# WB-v2_0b.net
KiCad netlist of a schematic drawn in EAGLE
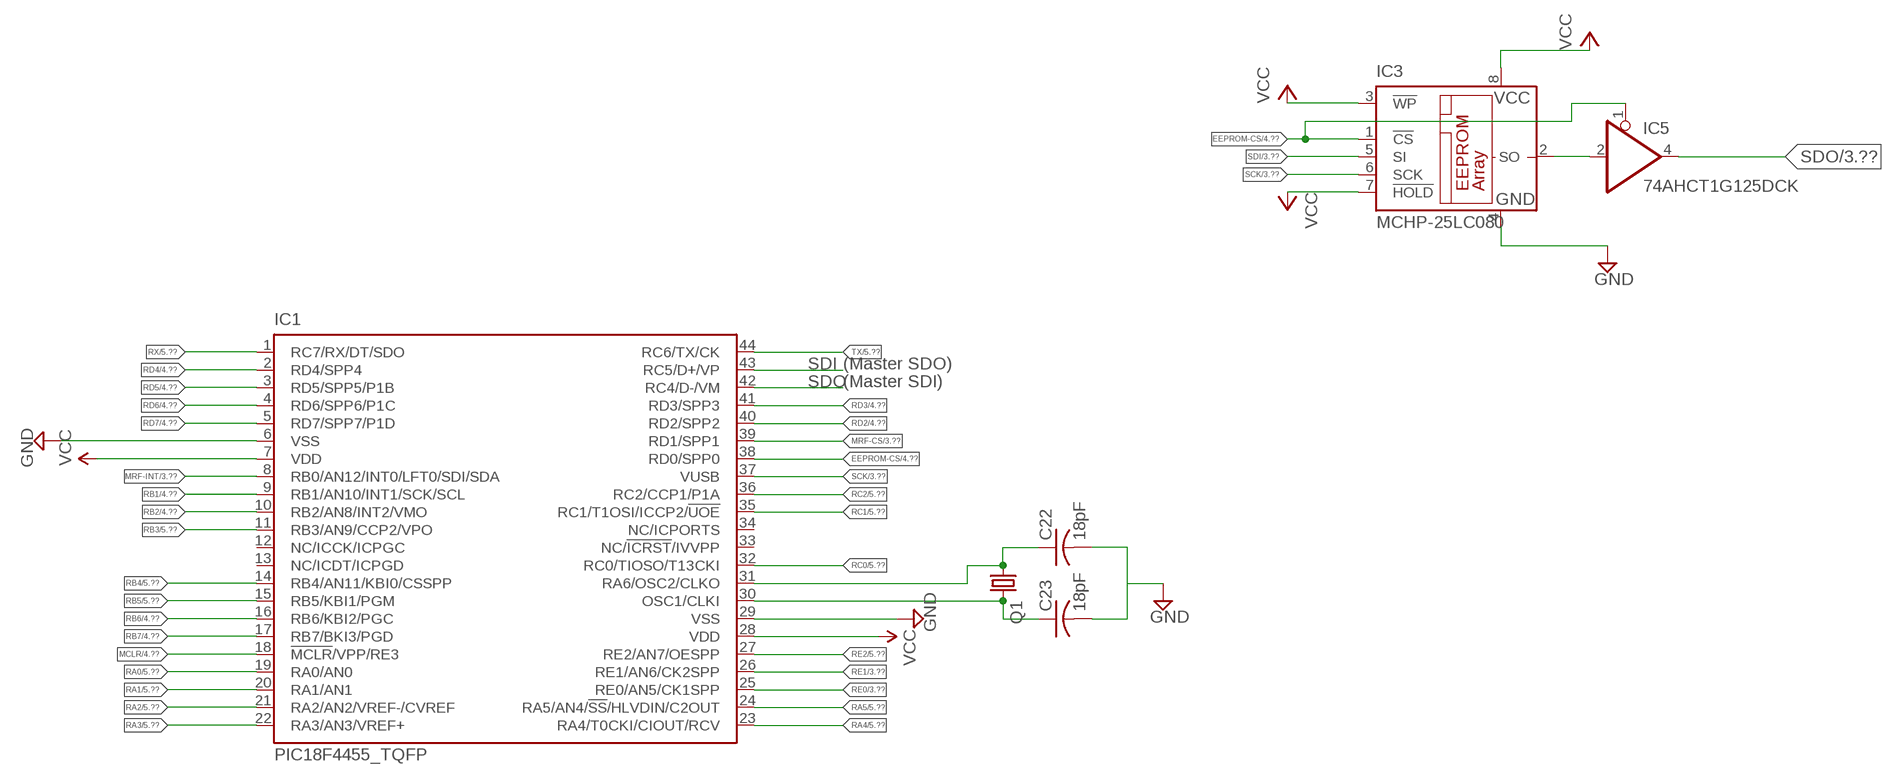
[diagram p0: schematic, sheet 1]
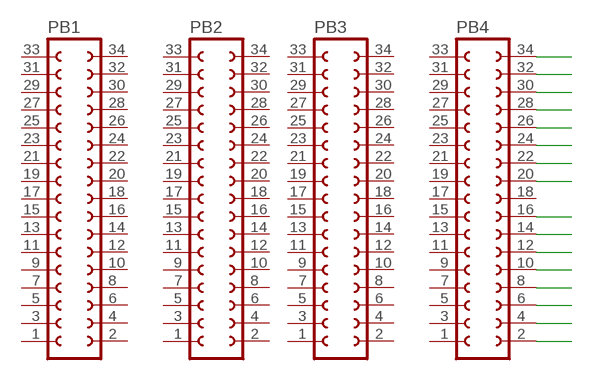
[diagram p1: schematic, sheet 2]
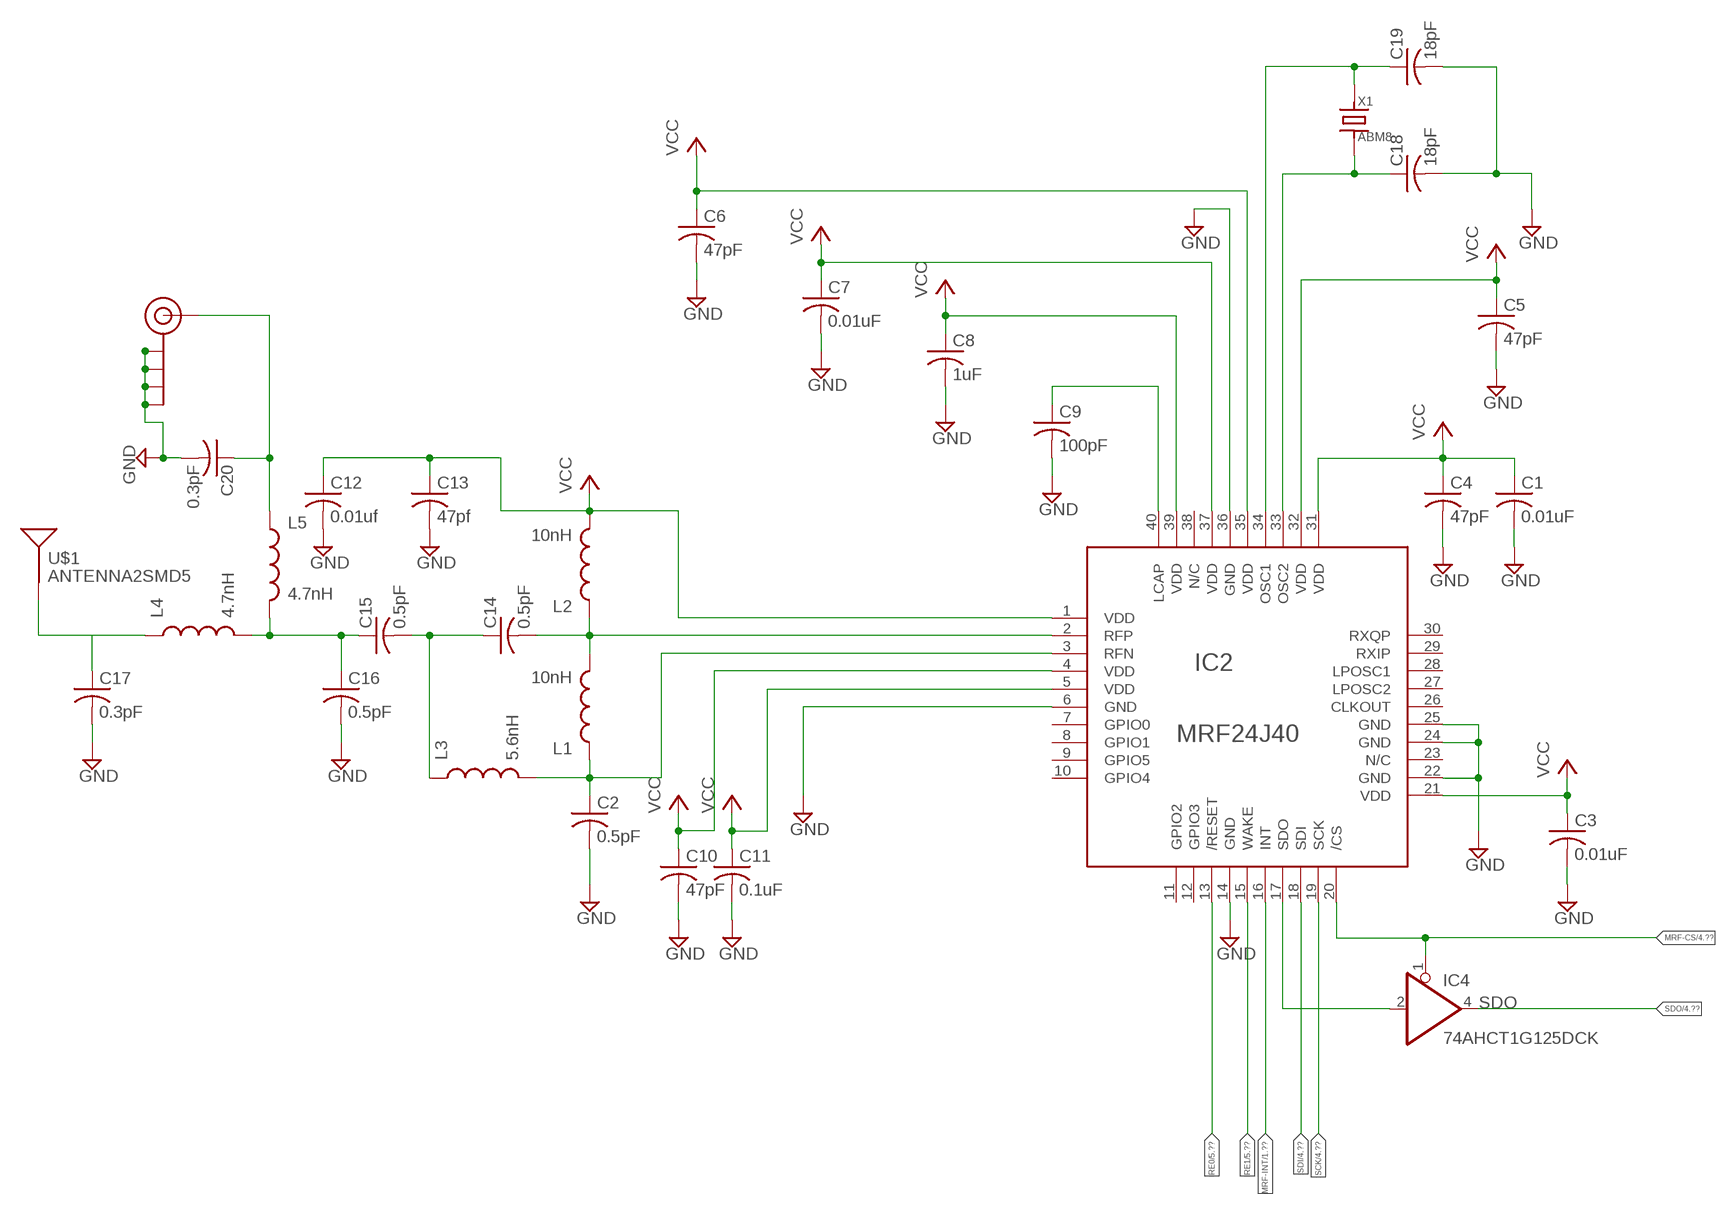
[diagram p2: schematic, sheet 3]
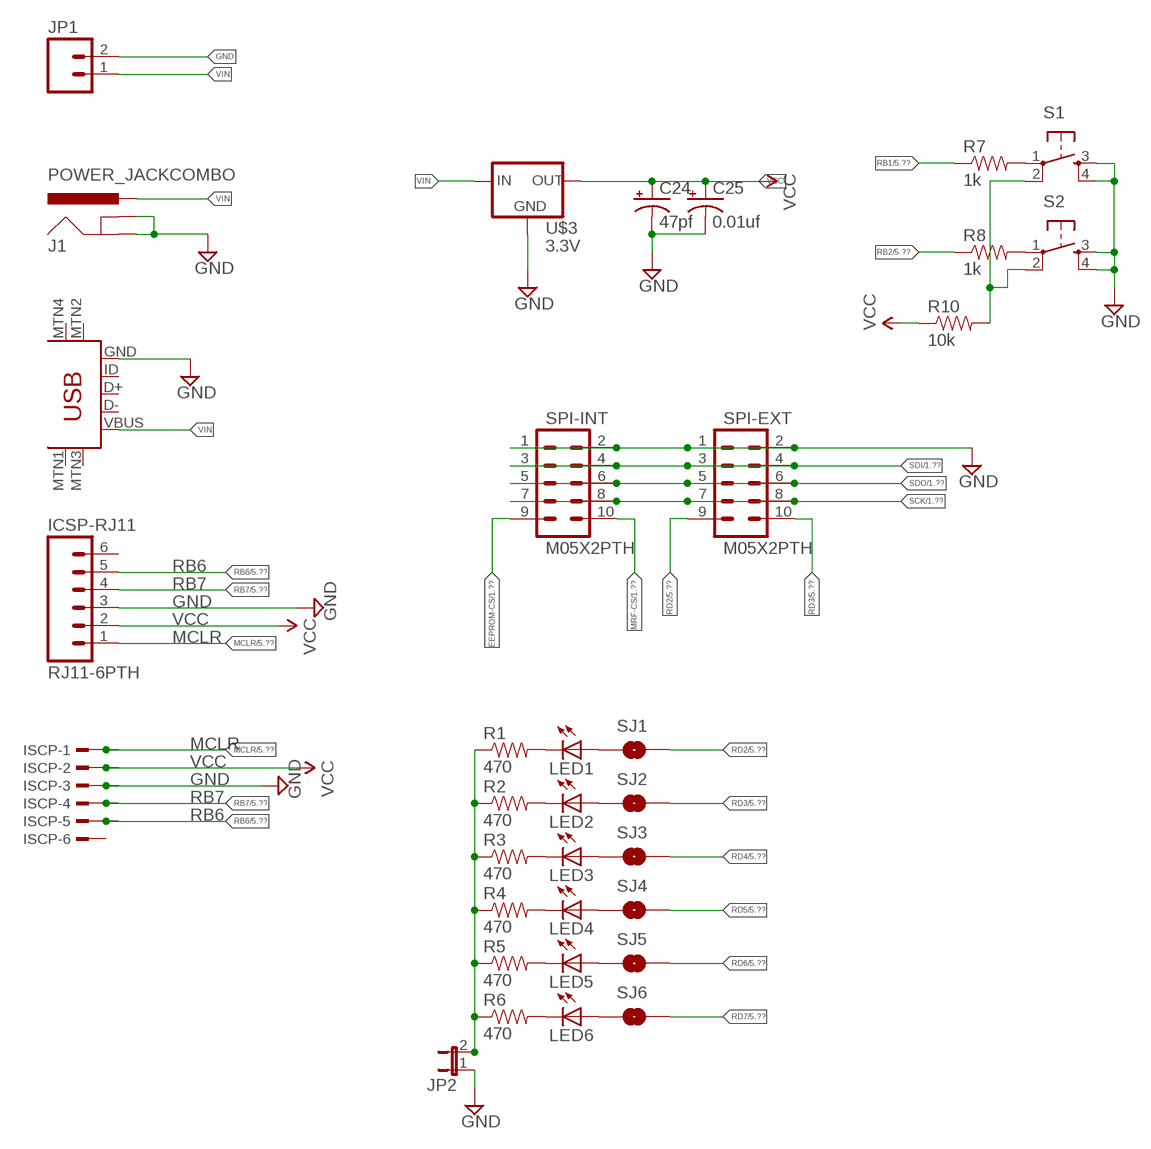
[diagram p3: schematic, sheet 4]
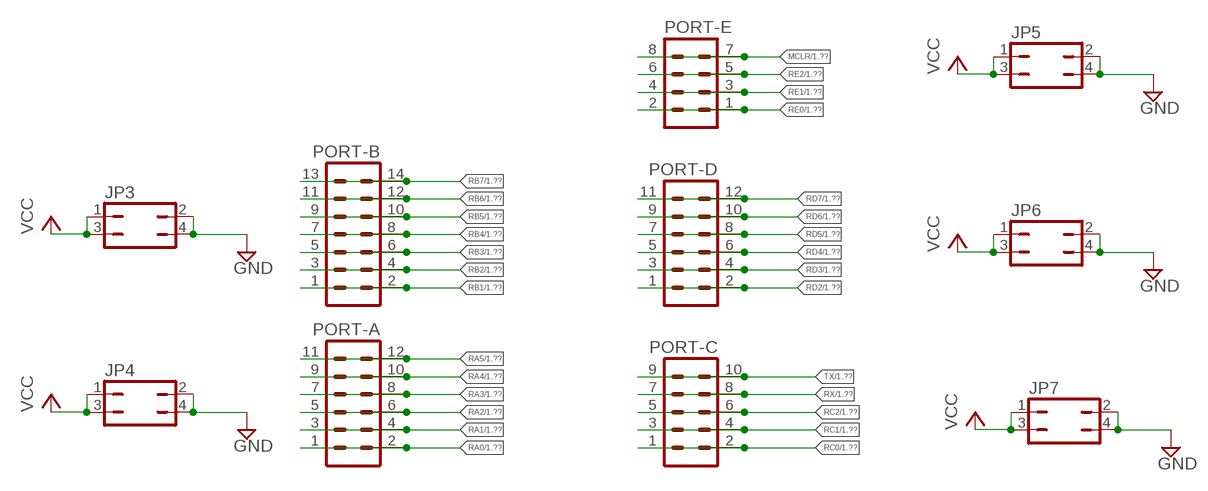
[diagram p4: schematic, sheet 5]

(export (version "E")
  (design (tool "Eeschema 10.0.6"))
  (components
    (comp (ref "C1")
      (value "0.01uF")
      (footprint "eagle-import:C0402")
      (libsource (lib "eagle-import") (part "C-USC0402"))
    )
    (comp (ref "C2")
      (value "0.5pF")
      (footprint "eagle-import:C0402")
      (libsource (lib "eagle-import") (part "C-USC0402"))
    )
    (comp (ref "C3")
      (value "0.01uF")
      (footprint "eagle-import:C0402")
      (libsource (lib "eagle-import") (part "C-USC0402"))
    )
    (comp (ref "C4")
      (value "47pF")
      (footprint "eagle-import:C0402")
      (libsource (lib "eagle-import") (part "C-USC0402"))
    )
    (comp (ref "C5")
      (value "47pF")
      (footprint "eagle-import:C0402")
      (libsource (lib "eagle-import") (part "C-USC0402"))
    )
    (comp (ref "C6")
      (value "47pF")
      (footprint "eagle-import:C0402")
      (libsource (lib "eagle-import") (part "C-USC0402"))
    )
    (comp (ref "C7")
      (value "0.01uF")
      (footprint "eagle-import:C0402")
      (libsource (lib "eagle-import") (part "C-USC0402"))
    )
    (comp (ref "C8")
      (value "1uF")
      (footprint "eagle-import:C0402")
      (libsource (lib "eagle-import") (part "C-USC0402"))
    )
    (comp (ref "C9")
      (value "100pF")
      (footprint "eagle-import:C0402")
      (libsource (lib "eagle-import") (part "C-USC0402"))
    )
    (comp (ref "C10")
      (value "47pF")
      (footprint "eagle-import:C0402")
      (libsource (lib "eagle-import") (part "C-USC0402"))
    )
    (comp (ref "C11")
      (value "0.1uF")
      (footprint "eagle-import:C0402")
      (libsource (lib "eagle-import") (part "C-USC0402"))
    )
    (comp (ref "C12")
      (value "0.01uf")
      (footprint "eagle-import:C0402")
      (libsource (lib "eagle-import") (part "C-USC0402"))
    )
    (comp (ref "C13")
      (value "47pf")
      (footprint "eagle-import:C0402")
      (libsource (lib "eagle-import") (part "C-USC0402"))
    )
    (comp (ref "C14")
      (value "0.5pF")
      (footprint "eagle-import:C0402")
      (libsource (lib "eagle-import") (part "C-USC0402"))
    )
    (comp (ref "C15")
      (value "0.5pF")
      (footprint "eagle-import:C0402")
      (libsource (lib "eagle-import") (part "C-USC0402"))
    )
    (comp (ref "C16")
      (value "0.5pF")
      (footprint "eagle-import:C0402")
      (libsource (lib "eagle-import") (part "C-USC0402"))
    )
    (comp (ref "C17")
      (value "0.3pF")
      (footprint "eagle-import:C0402")
      (libsource (lib "eagle-import") (part "C-USC0402"))
    )
    (comp (ref "C18")
      (value "18pF")
      (footprint "eagle-import:C0402")
      (libsource (lib "eagle-import") (part "C-USC0402"))
    )
    (comp (ref "C19")
      (value "18pF")
      (footprint "eagle-import:C0402")
      (libsource (lib "eagle-import") (part "C-USC0402"))
    )
    (comp (ref "C20")
      (value "0.3pF")
      (footprint "eagle-import:C0402")
      (libsource (lib "eagle-import") (part "C-USC0402"))
    )
    (comp (ref "IC2")
      (value "MRF24J40")
      (footprint "eagle-import:QFN40")
      (libsource (lib "eagle-import") (part "MRF24J40"))
    )
    (comp (ref "IC4")
      (value "74AHCT1G125DCK")
      (footprint "eagle-import:SC70-5")
      (libsource (lib "eagle-import") (part "741G125DCKAHCT"))
    )
    (comp (ref "J$1")
      (value "SMA_EDGE")
      (footprint "eagle-import:SMA-EDGE")
      (libsource (lib "eagle-import") (part "SMA_EDGE"))
    )
    (comp (ref "L1")
      (value "10nH")
      (footprint "eagle-import:C0402")
      (libsource (lib "eagle-import") (part "INDUCTOR0402"))
    )
    (comp (ref "L2")
      (value "10nH")
      (footprint "eagle-import:C0402")
      (libsource (lib "eagle-import") (part "INDUCTOR0402"))
    )
    (comp (ref "L3")
      (value "5.6nH")
      (footprint "eagle-import:C0402")
      (libsource (lib "eagle-import") (part "INDUCTOR0402"))
    )
    (comp (ref "L4")
      (value "4.7nH")
      (footprint "eagle-import:C0402")
      (libsource (lib "eagle-import") (part "INDUCTOR0402"))
    )
    (comp (ref "L5")
      (value "4.7nH")
      (footprint "eagle-import:C0402")
      (libsource (lib "eagle-import") (part "INDUCTOR0402"))
    )
    (comp (ref "U$1")
      (value "ANTENNA2SMD5")
      (footprint "eagle-import:ANTENNA-CHIP5")
      (libsource (lib "eagle-import") (part "ANTENNA2SMD5"))
    )
    (comp (ref "X1")
      (value "ABM8")
      (footprint "eagle-import:ABM8")
      (libsource (lib "eagle-import") (part "ABM8"))
    )
    (comp (ref "PB1")
      (value "FE17-2")
      (footprint "eagle-import:FE17-2")
      (libsource (lib "eagle-import") (part "FE17-2"))
    )
    (comp (ref "PB2")
      (value "FE17-2")
      (footprint "eagle-import:FE17-2")
      (libsource (lib "eagle-import") (part "FE17-2"))
    )
    (comp (ref "PB3")
      (value "FE17-2")
      (footprint "eagle-import:FE17-2")
      (libsource (lib "eagle-import") (part "FE17-2"))
    )
    (comp (ref "PB4")
      (value "FE17-2")
      (footprint "eagle-import:FE17-2")
      (libsource (lib "eagle-import") (part "FE17-2"))
    )
    (comp (ref "JP3")
      (value "JP2Q")
      (footprint "eagle-import:JP2Q")
      (libsource (lib "eagle-import") (part "JP2Q"))
    )
    (comp (ref "JP4")
      (value "JP2Q")
      (footprint "eagle-import:JP2Q")
      (libsource (lib "eagle-import") (part "JP2Q"))
    )
    (comp (ref "JP5")
      (value "JP2Q")
      (footprint "eagle-import:JP2Q")
      (libsource (lib "eagle-import") (part "JP2Q"))
    )
    (comp (ref "JP6")
      (value "JP2Q")
      (footprint "eagle-import:JP2Q")
      (libsource (lib "eagle-import") (part "JP2Q"))
    )
    (comp (ref "JP7")
      (value "JP2Q")
      (footprint "eagle-import:JP2Q")
      (libsource (lib "eagle-import") (part "JP2Q"))
    )
    (comp (ref "PORT-A")
      (value "MA06-2")
      (footprint "eagle-import:MA06-2")
      (libsource (lib "eagle-import") (part "MA06-2"))
    )
    (comp (ref "PORT-B")
      (value "MA07-2")
      (footprint "eagle-import:MA07-2")
      (libsource (lib "eagle-import") (part "MA07-2"))
    )
    (comp (ref "PORT-C")
      (value "MA05-2")
      (footprint "eagle-import:MA05-2")
      (libsource (lib "eagle-import") (part "MA05-2"))
    )
    (comp (ref "PORT-D")
      (value "MA06-2")
      (footprint "eagle-import:MA06-2")
      (libsource (lib "eagle-import") (part "MA06-2"))
    )
    (comp (ref "PORT-E")
      (value "MA04-2")
      (footprint "eagle-import:MA04-2")
      (libsource (lib "eagle-import") (part "MA04-2"))
    )
    (comp (ref "C22")
      (value "18pF")
      (footprint "eagle-import:C0402")
      (libsource (lib "eagle-import") (part "C-USC0402"))
    )
    (comp (ref "C23")
      (value "18pF")
      (footprint "eagle-import:C0402")
      (libsource (lib "eagle-import") (part "C-USC0402"))
    )
    (comp (ref "IC1")
      (value "PIC18F4455_TQFP")
      (footprint "eagle-import:TQFP44")
      (fields (field (name "MF") "MICROCHIP") (field (name "MPN") "PIC18F4455-I/PT"))
      (libsource (lib "eagle-import") (part "PIC18F4_TQFP455"))
    )
    (comp (ref "IC3")
      (value "MCHP-25LC080")
      (footprint "eagle-import:SO-08")
      (fields (field (name "MF") "MICROCHIP") (field (name "MPN") "25AA080/SN"))
      (libsource (lib "eagle-import") (part "25SNAA080"))
    )
    (comp (ref "IC5")
      (value "74AHCT1G125DCK")
      (footprint "eagle-import:SC70-5")
      (libsource (lib "eagle-import") (part "741G125DCKAHCT"))
    )
    (comp (ref "Q1")
      (value "CRYSTALSM49")
      (footprint "eagle-import:SM49")
      (libsource (lib "eagle-import") (part "CRYSTALSM49"))
    )
    (comp (ref "C24")
      (value "47pf")
      (footprint "eagle-import:CPOL-RADIAL-10UF-25V")
      (libsource (lib "eagle-import") (part "CAP_POLPTH2"))
    )
    (comp (ref "C25")
      (value "0.01uf")
      (footprint "eagle-import:CPOL-RADIAL-10UF-25V")
      (libsource (lib "eagle-import") (part "CAP_POLPTH2"))
    )
    (comp (ref "ICSP-RJ11")
      (value "RJ11-6PTH")
      (footprint "eagle-import:RJ11-6")
      (libsource (lib "eagle-import") (part "RJ11-6PTH"))
    )
    (comp (ref "ISCP")
      (value "TSW-106-02-S-S")
      (footprint "eagle-import:TSW-106-02-S-S")
      (libsource (lib "eagle-import") (part "TSW-106-02-S-S"))
    )
    (comp (ref "J1")
      (value "POWER_JACKCOMBO")
      (footprint "eagle-import:POWER_JACK_COMBO")
      (libsource (lib "eagle-import") (part "POWER_JACKCOMBO"))
    )
    (comp (ref "JP1")
      (value "M02LOCK_LONGPADS")
      (footprint "eagle-import:1X02_LOCK_LONGPADS")
      (libsource (lib "eagle-import") (part "M02LOCK_LONGPADS"))
    )
    (comp (ref "JP2")
      (value "JUMPER-2PTH")
      (footprint "eagle-import:1X02")
      (libsource (lib "eagle-import") (part "JUMPER-2PTH"))
    )
    (comp (ref "LED1")
      (value "LED0603")
      (footprint "eagle-import:LED-0603")
      (libsource (lib "eagle-import") (part "LED0603"))
    )
    (comp (ref "LED2")
      (value "LED0603")
      (footprint "eagle-import:LED-0603")
      (libsource (lib "eagle-import") (part "LED0603"))
    )
    (comp (ref "LED3")
      (value "LED0603")
      (footprint "eagle-import:LED-0603")
      (libsource (lib "eagle-import") (part "LED0603"))
    )
    (comp (ref "LED4")
      (value "LED0603")
      (footprint "eagle-import:LED-0603")
      (libsource (lib "eagle-import") (part "LED0603"))
    )
    (comp (ref "LED5")
      (value "LED0603")
      (footprint "eagle-import:LED-0603")
      (libsource (lib "eagle-import") (part "LED0603"))
    )
    (comp (ref "LED6")
      (value "LED0603")
      (footprint "eagle-import:LED-0603")
      (libsource (lib "eagle-import") (part "LED0603"))
    )
    (comp (ref "R1")
      (value "470")
      (footprint "eagle-import:0603-RES")
      (libsource (lib "eagle-import") (part "RESISTOR0603-RES"))
    )
    (comp (ref "R2")
      (value "470")
      (footprint "eagle-import:0603-RES")
      (libsource (lib "eagle-import") (part "RESISTOR0603-RES"))
    )
    (comp (ref "R3")
      (value "470")
      (footprint "eagle-import:0603-RES")
      (libsource (lib "eagle-import") (part "RESISTOR0603-RES"))
    )
    (comp (ref "R4")
      (value "470")
      (footprint "eagle-import:0603-RES")
      (libsource (lib "eagle-import") (part "RESISTOR0603-RES"))
    )
    (comp (ref "R5")
      (value "470")
      (footprint "eagle-import:0603-RES")
      (libsource (lib "eagle-import") (part "RESISTOR0603-RES"))
    )
    (comp (ref "R6")
      (value "470")
      (footprint "eagle-import:0603-RES")
      (libsource (lib "eagle-import") (part "RESISTOR0603-RES"))
    )
    (comp (ref "R7")
      (value "1k")
      (footprint "eagle-import:0603-RES")
      (libsource (lib "eagle-import") (part "RESISTOR0603-RES"))
    )
    (comp (ref "R8")
      (value "1k")
      (footprint "eagle-import:0603-RES")
      (libsource (lib "eagle-import") (part "RESISTOR0603-RES"))
    )
    (comp (ref "R10")
      (value "10k")
      (footprint "eagle-import:0603-RES")
      (libsource (lib "eagle-import") (part "RESISTOR0603-RES"))
    )
    (comp (ref "S1")
      (value "TAC_SWITCHPTH")
      (footprint "eagle-import:TACTILE-PTH")
      (libsource (lib "eagle-import") (part "TAC_SWITCHPTH"))
    )
    (comp (ref "S2")
      (value "TAC_SWITCHPTH")
      (footprint "eagle-import:TACTILE-PTH")
      (libsource (lib "eagle-import") (part "TAC_SWITCHPTH"))
    )
    (comp (ref "SJ1")
      (value "SOLDERJUMPERTRACE")
      (footprint "eagle-import:SJ_2S-TRACE")
      (libsource (lib "eagle-import") (part "SOLDERJUMPERTRACE"))
    )
    (comp (ref "SJ2")
      (value "SOLDERJUMPERTRACE")
      (footprint "eagle-import:SJ_2S-TRACE")
      (libsource (lib "eagle-import") (part "SOLDERJUMPERTRACE"))
    )
    (comp (ref "SJ3")
      (value "SOLDERJUMPERTRACE")
      (footprint "eagle-import:SJ_2S-TRACE")
      (libsource (lib "eagle-import") (part "SOLDERJUMPERTRACE"))
    )
    (comp (ref "SJ4")
      (value "SOLDERJUMPERTRACE")
      (footprint "eagle-import:SJ_2S-TRACE")
      (libsource (lib "eagle-import") (part "SOLDERJUMPERTRACE"))
    )
    (comp (ref "SJ5")
      (value "SOLDERJUMPERTRACE")
      (footprint "eagle-import:SJ_2S-TRACE")
      (libsource (lib "eagle-import") (part "SOLDERJUMPERTRACE"))
    )
    (comp (ref "SJ6")
      (value "SOLDERJUMPERTRACE")
      (footprint "eagle-import:SJ_2S-TRACE")
      (libsource (lib "eagle-import") (part "SOLDERJUMPERTRACE"))
    )
    (comp (ref "SPI-EXT")
      (value "M05X2PTH")
      (footprint "eagle-import:AVR_ICSP")
      (libsource (lib "eagle-import") (part "M05X2PTH"))
    )
    (comp (ref "SPI-INT")
      (value "M05X2PTH")
      (footprint "eagle-import:AVR_ICSP")
      (libsource (lib "eagle-import") (part "M05X2PTH"))
    )
    (comp (ref "U$2")
      (value "USB-MINIB-5PIN")
      (footprint "eagle-import:USB-MINIB")
      (libsource (lib "eagle-import") (part "USB-MINIB-5PIN"))
    )
    (comp (ref "U$3")
      (value "3.3V")
      (footprint "eagle-import:78XXL")
      (libsource (lib "eagle-import") (part "V_REG_LD1117VXX"))
    )
  )
  (nets
    (net (code "1") (name "EEPROM-CS") (class "Default")
      (node (ref "IC1") (pin "38") (pinfunction "RD0/SPP0_38") (pintype "bidirectional"))
      (node (ref "IC3") (pin "1") (pinfunction "~{CS}_1") (pintype "input"))
      (node (ref "IC5") (pin "1") (pinfunction "OE_1") (pintype "input"))
      (node (ref "SPI-INT") (pin "9") (pinfunction "9_9") (pintype "passive"))
    )
    (net (code "2") (name "GND") (class "Default")
      (node (ref "C1") (pin "2") (pinfunction "2_2") (pintype "passive"))
      (node (ref "C10") (pin "2") (pinfunction "2_2") (pintype "passive"))
      (node (ref "C11") (pin "2") (pinfunction "2_2") (pintype "passive"))
      (node (ref "C12") (pin "2") (pinfunction "2_2") (pintype "passive"))
      (node (ref "C13") (pin "2") (pinfunction "2_2") (pintype "passive"))
      (node (ref "C16") (pin "2") (pinfunction "2_2") (pintype "passive"))
      (node (ref "C17") (pin "2") (pinfunction "2_2") (pintype "passive"))
      (node (ref "C18") (pin "2") (pinfunction "2_2") (pintype "passive"))
      (node (ref "C19") (pin "2") (pinfunction "2_2") (pintype "passive"))
      (node (ref "C2") (pin "2") (pinfunction "2_2") (pintype "passive"))
      (node (ref "C20") (pin "2") (pinfunction "2_2") (pintype "passive"))
      (node (ref "C22") (pin "2") (pinfunction "2_2") (pintype "passive"))
      (node (ref "C23") (pin "2") (pinfunction "2_2") (pintype "passive"))
      (node (ref "C24") (pin "2") (pinfunction "-_2") (pintype "passive"))
      (node (ref "C25") (pin "2") (pinfunction "-_2") (pintype "passive"))
      (node (ref "C3") (pin "2") (pinfunction "2_2") (pintype "passive"))
      (node (ref "C4") (pin "2") (pinfunction "2_2") (pintype "passive"))
      (node (ref "C5") (pin "2") (pinfunction "2_2") (pintype "passive"))
      (node (ref "C6") (pin "2") (pinfunction "2_2") (pintype "passive"))
      (node (ref "C7") (pin "2") (pinfunction "2_2") (pintype "passive"))
      (node (ref "C8") (pin "2") (pinfunction "2_2") (pintype "passive"))
      (node (ref "C9") (pin "2") (pinfunction "2_2") (pintype "passive"))
      (node (ref "IC1") (pin "29") (pinfunction "VSS_29") (pintype "power_in"))
      (node (ref "IC1") (pin "6") (pinfunction "VSS_6") (pintype "power_in"))
      (node (ref "IC2") (pin "14") (pinfunction "GND_14") (pintype "power_in"))
      (node (ref "IC2") (pin "22") (pinfunction "GND_22") (pintype "power_in"))
      (node (ref "IC2") (pin "24") (pinfunction "GND_24") (pintype "power_in"))
      (node (ref "IC2") (pin "25") (pinfunction "GND_25") (pintype "power_in"))
      (node (ref "IC2") (pin "36") (pinfunction "GND_36") (pintype "power_in"))
      (node (ref "IC2") (pin "6") (pinfunction "GND_6") (pintype "power_in"))
      (node (ref "IC3") (pin "4") (pinfunction "GND_4") (pintype "power_in"))
      (node (ref "ICSP-RJ11") (pin "3") (pinfunction "3_3") (pintype "passive"))
      (node (ref "ISCP") (pin "3") (pinfunction "1_3") (pintype "passive"))
      (node (ref "J$1") (pin "GND@0") (pinfunction "GND_GND@0") (pintype "bidirectional"))
      (node (ref "J$1") (pin "GND@1") (pinfunction "GND_GND@1") (pintype "bidirectional"))
      (node (ref "J$1") (pin "GND@2") (pinfunction "GND_GND@2") (pintype "bidirectional"))
      (node (ref "J$1") (pin "GND@3") (pinfunction "GND_GND@3") (pintype "bidirectional"))
      (node (ref "J1") (pin "GND") (pinfunction "GNDBREAK_GND") (pintype "bidirectional"))
      (node (ref "J1") (pin "GND@1") (pinfunction "GND_GND@1") (pintype "bidirectional"))
      (node (ref "JP1") (pin "2") (pinfunction "2_2") (pintype "passive"))
      (node (ref "JP2") (pin "1") (pinfunction "1_1") (pintype "passive"))
      (node (ref "JP3") (pin "2") (pinfunction "2_2") (pintype "passive"))
      (node (ref "JP3") (pin "4") (pinfunction "4_4") (pintype "passive"))
      (node (ref "JP4") (pin "2") (pinfunction "2_2") (pintype "passive"))
      (node (ref "JP4") (pin "4") (pinfunction "4_4") (pintype "passive"))
      (node (ref "JP5") (pin "2") (pinfunction "2_2") (pintype "passive"))
      (node (ref "JP5") (pin "4") (pinfunction "4_4") (pintype "passive"))
      (node (ref "JP6") (pin "2") (pinfunction "2_2") (pintype "passive"))
      (node (ref "JP6") (pin "4") (pinfunction "4_4") (pintype "passive"))
      (node (ref "JP7") (pin "2") (pinfunction "2_2") (pintype "passive"))
      (node (ref "JP7") (pin "4") (pinfunction "4_4") (pintype "passive"))
      (node (ref "S1") (pin "3") (pinfunction "3_3") (pintype "passive"))
      (node (ref "S1") (pin "4") (pinfunction "4_4") (pintype "passive"))
      (node (ref "S2") (pin "3") (pinfunction "3_3") (pintype "passive"))
      (node (ref "S2") (pin "4") (pinfunction "4_4") (pintype "passive"))
      (node (ref "SPI-EXT") (pin "1") (pinfunction "1_1") (pintype "passive"))
      (node (ref "SPI-EXT") (pin "2") (pinfunction "2_2") (pintype "passive"))
      (node (ref "SPI-INT") (pin "1") (pinfunction "1_1") (pintype "passive"))
      (node (ref "SPI-INT") (pin "2") (pinfunction "2_2") (pintype "passive"))
      (node (ref "U$2") (pin "GND") (pinfunction "GND_GND") (pintype "bidirectional"))
      (node (ref "U$3") (pin "IN") (pinfunction "GND_IN") (pintype "input"))
    )
    (net (code "3") (name "MCLR") (class "Default")
      (node (ref "IC1") (pin "18") (pinfunction "~{MCLR}/VPP/RE3_18") (pintype "input"))
      (node (ref "ICSP-RJ11") (pin "1") (pinfunction "1_1") (pintype "passive"))
      (node (ref "ISCP") (pin "1") (pinfunction "1_1") (pintype "passive"))
      (node (ref "PORT-E") (pin "7") (pinfunction "7_7") (pintype "passive"))
      (node (ref "PORT-E") (pin "8") (pinfunction "8_8") (pintype "passive"))
    )
    (net (code "4") (name "MRF-CS") (class "Default")
      (node (ref "IC1") (pin "39") (pinfunction "RD1/SPP1_39") (pintype "bidirectional"))
      (node (ref "IC2") (pin "20") (pinfunction "/CS_20") (pintype "bidirectional"))
      (node (ref "IC4") (pin "1") (pinfunction "OE_1") (pintype "input"))
      (node (ref "SPI-INT") (pin "10") (pinfunction "10_10") (pintype "passive"))
    )
    (net (code "5") (name "MRF-INT") (class "Default")
      (node (ref "IC1") (pin "8") (pinfunction "RB0/AN12/INT0/LFT0/SDI/SDA_8") (pintype "bidirectional"))
      (node (ref "IC2") (pin "16") (pinfunction "INT_16") (pintype "bidirectional"))
    )
    (net (code "6") (name "Net-(C14-Pad1)") (class "Default")
      (node (ref "C14") (pin "1") (pinfunction "1_1") (pintype "passive"))
      (node (ref "C15") (pin "2") (pinfunction "2_2") (pintype "passive"))
      (node (ref "L3") (pin "1") (pinfunction "1_1") (pintype "passive"))
    )
    (net (code "7") (name "Net-(C15-Pad1)") (class "Default")
      (node (ref "C15") (pin "1") (pinfunction "1_1") (pintype "passive"))
      (node (ref "C16") (pin "1") (pinfunction "1_1") (pintype "passive"))
      (node (ref "L4") (pin "2") (pinfunction "2_2") (pintype "passive"))
      (node (ref "L5") (pin "2") (pinfunction "2_2") (pintype "passive"))
    )
    (net (code "8") (name "Net-(IC1-OSC1{slash}CLKI)") (class "Default")
      (node (ref "C23") (pin "1") (pinfunction "1_1") (pintype "passive"))
      (node (ref "IC1") (pin "30") (pinfunction "OSC1/CLKI_30") (pintype "input"))
      (node (ref "Q1") (pin "2") (pinfunction "2_2") (pintype "passive"))
    )
    (net (code "9") (name "Net-(IC1-RA6{slash}OSC2{slash}CLKO)") (class "Default")
      (node (ref "C22") (pin "1") (pinfunction "1_1") (pintype "passive"))
      (node (ref "IC1") (pin "31") (pinfunction "RA6/OSC2/CLKO_31") (pintype "output"))
      (node (ref "Q1") (pin "1") (pinfunction "1_1") (pintype "passive"))
    )
    (net (code "10") (name "Net-(IC2-LCAP)") (class "Default")
      (node (ref "C9") (pin "1") (pinfunction "1_1") (pintype "passive"))
      (node (ref "IC2") (pin "40") (pinfunction "LCAP_40") (pintype "bidirectional"))
    )
    (net (code "11") (name "Net-(IC2-OSC1)") (class "Default")
      (node (ref "C19") (pin "1") (pinfunction "1_1") (pintype "passive"))
      (node (ref "IC2") (pin "34") (pinfunction "OSC1_34") (pintype "open_collector"))
      (node (ref "X1") (pin "P$3") (pinfunction "P$3_P$3") (pintype "bidirectional"))
    )
    (net (code "12") (name "Net-(IC2-OSC2)") (class "Default")
      (node (ref "C18") (pin "1") (pinfunction "1_1") (pintype "passive"))
      (node (ref "IC2") (pin "33") (pinfunction "OSC2_33") (pintype "open_collector"))
      (node (ref "X1") (pin "P$1") (pinfunction "P$1_P$1") (pintype "bidirectional"))
    )
    (net (code "13") (name "Net-(IC2-RFN)") (class "Default")
      (node (ref "C2") (pin "1") (pinfunction "1_1") (pintype "passive"))
      (node (ref "IC2") (pin "3") (pinfunction "RFN_3") (pintype "bidirectional"))
      (node (ref "L1") (pin "1") (pinfunction "1_1") (pintype "passive"))
      (node (ref "L3") (pin "2") (pinfunction "2_2") (pintype "passive"))
    )
    (net (code "14") (name "Net-(IC2-RFP)") (class "Default")
      (node (ref "C14") (pin "2") (pinfunction "2_2") (pintype "passive"))
      (node (ref "IC2") (pin "2") (pinfunction "RFP_2") (pintype "bidirectional"))
      (node (ref "L1") (pin "2") (pinfunction "2_2") (pintype "passive"))
      (node (ref "L2") (pin "1") (pinfunction "1_1") (pintype "passive"))
    )
    (net (code "15") (name "Net-(IC2-SDO)") (class "Default")
      (node (ref "IC2") (pin "17") (pinfunction "SDO_17") (pintype "bidirectional"))
      (node (ref "IC4") (pin "2") (pinfunction "I_2") (pintype "input"))
    )
    (net (code "16") (name "Net-(IC3-SO)") (class "Default")
      (node (ref "IC3") (pin "2") (pinfunction "SO_2") (pintype "bidirectional"))
      (node (ref "IC5") (pin "2") (pinfunction "I_2") (pintype "input"))
    )
    (net (code "17") (name "Net-(J$1-SIGNAL)") (class "Default")
      (node (ref "C20") (pin "1") (pinfunction "1_1") (pintype "passive"))
      (node (ref "J$1") (pin "SIG") (pinfunction "SIGNAL_SIG") (pintype "bidirectional"))
      (node (ref "L5") (pin "1") (pinfunction "1_1") (pintype "passive"))
    )
    (net (code "18") (name "Net-(JP2-Pad2)") (class "Default")
      (node (ref "JP2") (pin "2") (pinfunction "2_2") (pintype "passive"))
      (node (ref "R1") (pin "1") (pinfunction "1_1") (pintype "passive"))
      (node (ref "R2") (pin "1") (pinfunction "1_1") (pintype "passive"))
      (node (ref "R3") (pin "1") (pinfunction "1_1") (pintype "passive"))
      (node (ref "R4") (pin "1") (pinfunction "1_1") (pintype "passive"))
      (node (ref "R5") (pin "1") (pinfunction "1_1") (pintype "passive"))
      (node (ref "R6") (pin "1") (pinfunction "1_1") (pintype "passive"))
    )
    (net (code "19") (name "Net-(LED1-PadA)") (class "Default")
      (node (ref "LED1") (pin "A") (pinfunction "A_A") (pintype "passive"))
      (node (ref "SJ1") (pin "1") (pinfunction "1_1") (pintype "passive"))
    )
    (net (code "20") (name "Net-(LED1-PadC)") (class "Default")
      (node (ref "LED1") (pin "C") (pinfunction "C_C") (pintype "passive"))
      (node (ref "R1") (pin "2") (pinfunction "2_2") (pintype "passive"))
    )
    (net (code "21") (name "Net-(LED2-PadA)") (class "Default")
      (node (ref "LED2") (pin "A") (pinfunction "A_A") (pintype "passive"))
      (node (ref "SJ2") (pin "1") (pinfunction "1_1") (pintype "passive"))
    )
    (net (code "22") (name "Net-(LED2-PadC)") (class "Default")
      (node (ref "LED2") (pin "C") (pinfunction "C_C") (pintype "passive"))
      (node (ref "R2") (pin "2") (pinfunction "2_2") (pintype "passive"))
    )
    (net (code "23") (name "Net-(LED3-PadA)") (class "Default")
      (node (ref "LED3") (pin "A") (pinfunction "A_A") (pintype "passive"))
      (node (ref "SJ3") (pin "1") (pinfunction "1_1") (pintype "passive"))
    )
    (net (code "24") (name "Net-(LED3-PadC)") (class "Default")
      (node (ref "LED3") (pin "C") (pinfunction "C_C") (pintype "passive"))
      (node (ref "R3") (pin "2") (pinfunction "2_2") (pintype "passive"))
    )
    (net (code "25") (name "Net-(LED4-PadA)") (class "Default")
      (node (ref "LED4") (pin "A") (pinfunction "A_A") (pintype "passive"))
      (node (ref "SJ4") (pin "1") (pinfunction "1_1") (pintype "passive"))
    )
    (net (code "26") (name "Net-(LED4-PadC)") (class "Default")
      (node (ref "LED4") (pin "C") (pinfunction "C_C") (pintype "passive"))
      (node (ref "R4") (pin "2") (pinfunction "2_2") (pintype "passive"))
    )
    (net (code "27") (name "Net-(LED5-PadA)") (class "Default")
      (node (ref "LED5") (pin "A") (pinfunction "A_A") (pintype "passive"))
      (node (ref "SJ5") (pin "1") (pinfunction "1_1") (pintype "passive"))
    )
    (net (code "28") (name "Net-(LED5-PadC)") (class "Default")
      (node (ref "LED5") (pin "C") (pinfunction "C_C") (pintype "passive"))
      (node (ref "R5") (pin "2") (pinfunction "2_2") (pintype "passive"))
    )
    (net (code "29") (name "Net-(LED6-PadA)") (class "Default")
      (node (ref "LED6") (pin "A") (pinfunction "A_A") (pintype "passive"))
      (node (ref "SJ6") (pin "1") (pinfunction "1_1") (pintype "passive"))
    )
    (net (code "30") (name "Net-(LED6-PadC)") (class "Default")
      (node (ref "LED6") (pin "C") (pinfunction "C_C") (pintype "passive"))
      (node (ref "R6") (pin "2") (pinfunction "2_2") (pintype "passive"))
    )
    (net (code "31") (name "Net-(R7-Pad2)") (class "Default")
      (node (ref "R7") (pin "2") (pinfunction "2_2") (pintype "passive"))
      (node (ref "S1") (pin "1") (pinfunction "1_1") (pintype "passive"))
    )
    (net (code "32") (name "Net-(R8-Pad2)") (class "Default")
      (node (ref "R8") (pin "2") (pinfunction "2_2") (pintype "passive"))
      (node (ref "S2") (pin "1") (pinfunction "1_1") (pintype "passive"))
    )
    (net (code "33") (name "Net-(R10-Pad2)") (class "Default")
      (node (ref "R10") (pin "2") (pinfunction "2_2") (pintype "passive"))
      (node (ref "S1") (pin "2") (pinfunction "2_2") (pintype "passive"))
      (node (ref "S2") (pin "2") (pinfunction "2_2") (pintype "passive"))
    )
    (net (code "34") (name "Net-(U$1-SIGNAL)") (class "Default")
      (node (ref "C17") (pin "1") (pinfunction "1_1") (pintype "passive"))
      (node (ref "L4") (pin "1") (pinfunction "1_1") (pintype "passive"))
      (node (ref "U$1") (pin "FEED") (pinfunction "SIGNAL_FEED") (pintype "bidirectional"))
    )
    (net (code "35") (name "RA0") (class "Default")
      (node (ref "IC1") (pin "19") (pinfunction "RA0/AN0_19") (pintype "bidirectional"))
      (node (ref "PORT-A") (pin "1") (pinfunction "1_1") (pintype "passive"))
      (node (ref "PORT-A") (pin "2") (pinfunction "2_2") (pintype "passive"))
    )
    (net (code "36") (name "RA1") (class "Default")
      (node (ref "IC1") (pin "20") (pinfunction "RA1/AN1_20") (pintype "bidirectional"))
      (node (ref "PORT-A") (pin "3") (pinfunction "3_3") (pintype "passive"))
      (node (ref "PORT-A") (pin "4") (pinfunction "4_4") (pintype "passive"))
    )
    (net (code "37") (name "RA2") (class "Default")
      (node (ref "IC1") (pin "21") (pinfunction "RA2/AN2/VREF-/CVREF_21") (pintype "bidirectional"))
      (node (ref "PORT-A") (pin "5") (pinfunction "5_5") (pintype "passive"))
      (node (ref "PORT-A") (pin "6") (pinfunction "6_6") (pintype "passive"))
    )
    (net (code "38") (name "RA3") (class "Default")
      (node (ref "IC1") (pin "22") (pinfunction "RA3/AN3/VREF+_22") (pintype "bidirectional"))
      (node (ref "PORT-A") (pin "7") (pinfunction "7_7") (pintype "passive"))
      (node (ref "PORT-A") (pin "8") (pinfunction "8_8") (pintype "passive"))
    )
    (net (code "39") (name "RA4") (class "Default")
      (node (ref "IC1") (pin "23") (pinfunction "RA4/T0CKI/CIOUT/RCV_23") (pintype "bidirectional"))
      (node (ref "PORT-A") (pin "10") (pinfunction "10_10") (pintype "passive"))
      (node (ref "PORT-A") (pin "9") (pinfunction "9_9") (pintype "passive"))
    )
    (net (code "40") (name "RA5") (class "Default")
      (node (ref "IC1") (pin "24") (pinfunction "RA5/AN4/~{SS}/HLVDIN/C2OUT_24") (pintype "bidirectional"))
      (node (ref "PORT-A") (pin "11") (pinfunction "11_11") (pintype "passive"))
      (node (ref "PORT-A") (pin "12") (pinfunction "12_12") (pintype "passive"))
    )
    (net (code "41") (name "RB1") (class "Default")
      (node (ref "IC1") (pin "9") (pinfunction "RB1/AN10/INT1/SCK/SCL_9") (pintype "bidirectional"))
      (node (ref "PORT-B") (pin "1") (pinfunction "1_1") (pintype "passive"))
      (node (ref "PORT-B") (pin "2") (pinfunction "2_2") (pintype "passive"))
      (node (ref "R7") (pin "1") (pinfunction "1_1") (pintype "passive"))
    )
    (net (code "42") (name "RB2") (class "Default")
      (node (ref "IC1") (pin "10") (pinfunction "RB2/AN8/INT2/VMO_10") (pintype "bidirectional"))
      (node (ref "PORT-B") (pin "3") (pinfunction "3_3") (pintype "passive"))
      (node (ref "PORT-B") (pin "4") (pinfunction "4_4") (pintype "passive"))
      (node (ref "R8") (pin "1") (pinfunction "1_1") (pintype "passive"))
    )
    (net (code "43") (name "RB3") (class "Default")
      (node (ref "IC1") (pin "11") (pinfunction "RB3/AN9/CCP2/VPO_11") (pintype "bidirectional"))
      (node (ref "PORT-B") (pin "5") (pinfunction "5_5") (pintype "passive"))
      (node (ref "PORT-B") (pin "6") (pinfunction "6_6") (pintype "passive"))
    )
    (net (code "44") (name "RB4") (class "Default")
      (node (ref "IC1") (pin "14") (pinfunction "RB4/AN11/KBI0/CSSPP_14") (pintype "bidirectional"))
      (node (ref "PORT-B") (pin "7") (pinfunction "7_7") (pintype "passive"))
      (node (ref "PORT-B") (pin "8") (pinfunction "8_8") (pintype "passive"))
    )
    (net (code "45") (name "RB5") (class "Default")
      (node (ref "IC1") (pin "15") (pinfunction "RB5/KBI1/PGM_15") (pintype "bidirectional"))
      (node (ref "PORT-B") (pin "10") (pinfunction "10_10") (pintype "passive"))
      (node (ref "PORT-B") (pin "9") (pinfunction "9_9") (pintype "passive"))
    )
    (net (code "46") (name "RB6") (class "Default")
      (node (ref "IC1") (pin "16") (pinfunction "RB6/KBI2/PGC_16") (pintype "bidirectional"))
      (node (ref "ICSP-RJ11") (pin "5") (pinfunction "5_5") (pintype "passive"))
      (node (ref "ISCP") (pin "5") (pinfunction "1_5") (pintype "passive"))
      (node (ref "PORT-B") (pin "11") (pinfunction "11_11") (pintype "passive"))
      (node (ref "PORT-B") (pin "12") (pinfunction "12_12") (pintype "passive"))
    )
    (net (code "47") (name "RB7") (class "Default")
      (node (ref "IC1") (pin "17") (pinfunction "RB7/BKI3/PGD_17") (pintype "bidirectional"))
      (node (ref "ICSP-RJ11") (pin "4") (pinfunction "4_4") (pintype "passive"))
      (node (ref "ISCP") (pin "4") (pinfunction "1_4") (pintype "passive"))
      (node (ref "PORT-B") (pin "13") (pinfunction "13_13") (pintype "passive"))
      (node (ref "PORT-B") (pin "14") (pinfunction "14_14") (pintype "passive"))
    )
    (net (code "48") (name "RC0") (class "Default")
      (node (ref "IC1") (pin "32") (pinfunction "RC0/TIOSO/T13CKI_32") (pintype "bidirectional"))
      (node (ref "PORT-C") (pin "1") (pinfunction "1_1") (pintype "passive"))
      (node (ref "PORT-C") (pin "2") (pinfunction "2_2") (pintype "passive"))
    )
    (net (code "49") (name "RC1") (class "Default")
      (node (ref "IC1") (pin "35") (pinfunction "RC1/T1OSI/ICCP2/~{UOE}_35") (pintype "bidirectional"))
      (node (ref "PORT-C") (pin "3") (pinfunction "3_3") (pintype "passive"))
      (node (ref "PORT-C") (pin "4") (pinfunction "4_4") (pintype "passive"))
    )
    (net (code "50") (name "RC2") (class "Default")
      (node (ref "IC1") (pin "36") (pinfunction "RC2/CCP1/P1A_36") (pintype "bidirectional"))
      (node (ref "PORT-C") (pin "5") (pinfunction "5_5") (pintype "passive"))
      (node (ref "PORT-C") (pin "6") (pinfunction "6_6") (pintype "passive"))
    )
    (net (code "51") (name "RD2") (class "Default")
      (node (ref "IC1") (pin "40") (pinfunction "RD2/SPP2_40") (pintype "bidirectional"))
      (node (ref "PORT-D") (pin "1") (pinfunction "1_1") (pintype "passive"))
      (node (ref "PORT-D") (pin "2") (pinfunction "2_2") (pintype "passive"))
      (node (ref "SJ1") (pin "2") (pinfunction "2_2") (pintype "passive"))
      (node (ref "SPI-EXT") (pin "9") (pinfunction "9_9") (pintype "passive"))
    )
    (net (code "52") (name "RD3") (class "Default")
      (node (ref "IC1") (pin "41") (pinfunction "RD3/SPP3_41") (pintype "bidirectional"))
      (node (ref "PORT-D") (pin "3") (pinfunction "3_3") (pintype "passive"))
      (node (ref "PORT-D") (pin "4") (pinfunction "4_4") (pintype "passive"))
      (node (ref "SJ2") (pin "2") (pinfunction "2_2") (pintype "passive"))
      (node (ref "SPI-EXT") (pin "10") (pinfunction "10_10") (pintype "passive"))
    )
    (net (code "53") (name "RD4") (class "Default")
      (node (ref "IC1") (pin "2") (pinfunction "RD4/SPP4_2") (pintype "bidirectional"))
      (node (ref "PORT-D") (pin "5") (pinfunction "5_5") (pintype "passive"))
      (node (ref "PORT-D") (pin "6") (pinfunction "6_6") (pintype "passive"))
      (node (ref "SJ3") (pin "2") (pinfunction "2_2") (pintype "passive"))
    )
    (net (code "54") (name "RD5") (class "Default")
      (node (ref "IC1") (pin "3") (pinfunction "RD5/SPP5/P1B_3") (pintype "bidirectional"))
      (node (ref "PORT-D") (pin "7") (pinfunction "7_7") (pintype "passive"))
      (node (ref "PORT-D") (pin "8") (pinfunction "8_8") (pintype "passive"))
      (node (ref "SJ4") (pin "2") (pinfunction "2_2") (pintype "passive"))
    )
    (net (code "55") (name "RD6") (class "Default")
      (node (ref "IC1") (pin "4") (pinfunction "RD6/SPP6/P1C_4") (pintype "bidirectional"))
      (node (ref "PORT-D") (pin "10") (pinfunction "10_10") (pintype "passive"))
      (node (ref "PORT-D") (pin "9") (pinfunction "9_9") (pintype "passive"))
      (node (ref "SJ5") (pin "2") (pinfunction "2_2") (pintype "passive"))
    )
    (net (code "56") (name "RD7") (class "Default")
      (node (ref "IC1") (pin "5") (pinfunction "RD7/SPP7/P1D_5") (pintype "bidirectional"))
      (node (ref "PORT-D") (pin "11") (pinfunction "11_11") (pintype "passive"))
      (node (ref "PORT-D") (pin "12") (pinfunction "12_12") (pintype "passive"))
      (node (ref "SJ6") (pin "2") (pinfunction "2_2") (pintype "passive"))
    )
    (net (code "57") (name "RE0") (class "Default")
      (node (ref "IC1") (pin "25") (pinfunction "RE0/AN5/CK1SPP_25") (pintype "bidirectional"))
      (node (ref "IC2") (pin "13") (pinfunction "/RESET_13") (pintype "bidirectional"))
      (node (ref "PORT-E") (pin "1") (pinfunction "1_1") (pintype "passive"))
      (node (ref "PORT-E") (pin "2") (pinfunction "2_2") (pintype "passive"))
    )
    (net (code "58") (name "RE1") (class "Default")
      (node (ref "IC1") (pin "26") (pinfunction "RE1/AN6/CK2SPP_26") (pintype "bidirectional"))
      (node (ref "IC2") (pin "15") (pinfunction "WAKE_15") (pintype "bidirectional"))
      (node (ref "PORT-E") (pin "3") (pinfunction "3_3") (pintype "passive"))
      (node (ref "PORT-E") (pin "4") (pinfunction "4_4") (pintype "passive"))
    )
    (net (code "59") (name "RE2") (class "Default")
      (node (ref "IC1") (pin "27") (pinfunction "RE2/AN7/OESPP_27") (pintype "bidirectional"))
      (node (ref "PORT-E") (pin "5") (pinfunction "5_5") (pintype "passive"))
      (node (ref "PORT-E") (pin "6") (pinfunction "6_6") (pintype "passive"))
    )
    (net (code "60") (name "RX") (class "Default")
      (node (ref "IC1") (pin "1") (pinfunction "RC7/RX/DT/SDO_1") (pintype "bidirectional"))
      (node (ref "PORT-C") (pin "7") (pinfunction "7_7") (pintype "passive"))
      (node (ref "PORT-C") (pin "8") (pinfunction "8_8") (pintype "passive"))
    )
    (net (code "61") (name "SCK") (class "Default")
      (node (ref "IC1") (pin "37") (pinfunction "VUSB_37") (pintype "bidirectional"))
      (node (ref "IC2") (pin "19") (pinfunction "SCK_19") (pintype "bidirectional"))
      (node (ref "IC3") (pin "6") (pinfunction "SCK_6") (pintype "input"))
      (node (ref "SPI-EXT") (pin "7") (pinfunction "7_7") (pintype "passive"))
      (node (ref "SPI-EXT") (pin "8") (pinfunction "8_8") (pintype "passive"))
      (node (ref "SPI-INT") (pin "7") (pinfunction "7_7") (pintype "passive"))
      (node (ref "SPI-INT") (pin "8") (pinfunction "8_8") (pintype "passive"))
    )
    (net (code "62") (name "SDI") (class "Default")
      (node (ref "IC1") (pin "43") (pinfunction "RC5/D+/VP_43") (pintype "bidirectional"))
      (node (ref "IC2") (pin "18") (pinfunction "SDI_18") (pintype "bidirectional"))
      (node (ref "IC3") (pin "5") (pinfunction "SI_5") (pintype "input"))
      (node (ref "SPI-EXT") (pin "3") (pinfunction "3_3") (pintype "passive"))
      (node (ref "SPI-EXT") (pin "4") (pinfunction "4_4") (pintype "passive"))
      (node (ref "SPI-INT") (pin "3") (pinfunction "3_3") (pintype "passive"))
      (node (ref "SPI-INT") (pin "4") (pinfunction "4_4") (pintype "passive"))
    )
    (net (code "63") (name "SDO") (class "Default")
      (node (ref "IC1") (pin "42") (pinfunction "RC4/D-/VM_42") (pintype "bidirectional"))
      (node (ref "IC4") (pin "4") (pinfunction "O_4") (pintype "tri_state"))
      (node (ref "IC5") (pin "4") (pinfunction "O_4") (pintype "tri_state"))
      (node (ref "SPI-EXT") (pin "5") (pinfunction "5_5") (pintype "passive"))
      (node (ref "SPI-EXT") (pin "6") (pinfunction "6_6") (pintype "passive"))
      (node (ref "SPI-INT") (pin "5") (pinfunction "5_5") (pintype "passive"))
      (node (ref "SPI-INT") (pin "6") (pinfunction "6_6") (pintype "passive"))
    )
    (net (code "64") (name "TX") (class "Default")
      (node (ref "IC1") (pin "44") (pinfunction "RC6/TX/CK_44") (pintype "bidirectional"))
      (node (ref "PORT-C") (pin "10") (pinfunction "10_10") (pintype "passive"))
      (node (ref "PORT-C") (pin "9") (pinfunction "9_9") (pintype "passive"))
    )
    (net (code "65") (name "VCC") (class "Default")
      (node (ref "C1") (pin "1") (pinfunction "1_1") (pintype "passive"))
      (node (ref "C10") (pin "1") (pinfunction "1_1") (pintype "passive"))
      (node (ref "C11") (pin "1") (pinfunction "1_1") (pintype "passive"))
      (node (ref "C12") (pin "1") (pinfunction "1_1") (pintype "passive"))
      (node (ref "C13") (pin "1") (pinfunction "1_1") (pintype "passive"))
      (node (ref "C24") (pin "1") (pinfunction "+_1") (pintype "passive"))
      (node (ref "C25") (pin "1") (pinfunction "+_1") (pintype "passive"))
      (node (ref "C3") (pin "1") (pinfunction "1_1") (pintype "passive"))
      (node (ref "C4") (pin "1") (pinfunction "1_1") (pintype "passive"))
      (node (ref "C5") (pin "1") (pinfunction "1_1") (pintype "passive"))
      (node (ref "C6") (pin "1") (pinfunction "1_1") (pintype "passive"))
      (node (ref "C7") (pin "1") (pinfunction "1_1") (pintype "passive"))
      (node (ref "C8") (pin "1") (pinfunction "1_1") (pintype "passive"))
      (node (ref "IC1") (pin "28") (pinfunction "VDD_28") (pintype "power_in"))
      (node (ref "IC1") (pin "7") (pinfunction "VDD_7") (pintype "power_in"))
      (node (ref "IC2") (pin "1") (pinfunction "VDD_1") (pintype "power_in"))
      (node (ref "IC2") (pin "21") (pinfunction "VDD_21") (pintype "power_in"))
      (node (ref "IC2") (pin "31") (pinfunction "VDD_31") (pintype "power_in"))
      (node (ref "IC2") (pin "32") (pinfunction "VDD_32") (pintype "power_in"))
      (node (ref "IC2") (pin "35") (pinfunction "VDD_35") (pintype "power_in"))
      (node (ref "IC2") (pin "37") (pinfunction "VDD_37") (pintype "bidirectional"))
      (node (ref "IC2") (pin "39") (pinfunction "VDD_39") (pintype "power_in"))
      (node (ref "IC2") (pin "4") (pinfunction "VDD_4") (pintype "power_in"))
      (node (ref "IC2") (pin "5") (pinfunction "VDD_5") (pintype "power_in"))
      (node (ref "IC3") (pin "3") (pinfunction "~{WP}_3") (pintype "input"))
      (node (ref "IC3") (pin "7") (pinfunction "~{HOLD}_7") (pintype "input"))
      (node (ref "IC3") (pin "8") (pinfunction "VCC_8") (pintype "power_in"))
      (node (ref "ICSP-RJ11") (pin "2") (pinfunction "2_2") (pintype "passive"))
      (node (ref "ISCP") (pin "2") (pinfunction "1_2") (pintype "passive"))
      (node (ref "JP3") (pin "1") (pinfunction "1_1") (pintype "passive"))
      (node (ref "JP3") (pin "3") (pinfunction "3_3") (pintype "passive"))
      (node (ref "JP4") (pin "1") (pinfunction "1_1") (pintype "passive"))
      (node (ref "JP4") (pin "3") (pinfunction "3_3") (pintype "passive"))
      (node (ref "JP5") (pin "1") (pinfunction "1_1") (pintype "passive"))
      (node (ref "JP5") (pin "3") (pinfunction "3_3") (pintype "passive"))
      (node (ref "JP6") (pin "1") (pinfunction "1_1") (pintype "passive"))
      (node (ref "JP6") (pin "3") (pinfunction "3_3") (pintype "passive"))
      (node (ref "JP7") (pin "1") (pinfunction "1_1") (pintype "passive"))
      (node (ref "JP7") (pin "3") (pinfunction "3_3") (pintype "passive"))
      (node (ref "L2") (pin "2") (pinfunction "2_2") (pintype "passive"))
      (node (ref "R10") (pin "1") (pinfunction "1_1") (pintype "passive"))
      (node (ref "U$3") (pin "GND") (pinfunction "OUT_GND") (pintype "output"))
    )
    (net (code "66") (name "VIN") (class "Default")
      (node (ref "J1") (pin "POWER") (pinfunction "PWR_POWER") (pintype "bidirectional"))
      (node (ref "JP1") (pin "1") (pinfunction "1_1") (pintype "passive"))
      (node (ref "U$2") (pin "VBUS") (pinfunction "VBUS_VBUS") (pintype "bidirectional"))
      (node (ref "U$3") (pin "OUT") (pinfunction "IN_OUT") (pintype "input"))
    )
    (net (code "67") (name "unconnected-(IC1-NC{slash}ICCK{slash}ICPGC-Pad12)") (class "Default")
      (node (ref "IC1") (pin "12") (pinfunction "NC/ICCK/ICPGC_12") (pintype "bidirectional"))
    )
    (net (code "68") (name "unconnected-(IC1-NC{slash}ICDT{slash}ICPGD-Pad13)") (class "Default")
      (node (ref "IC1") (pin "13") (pinfunction "NC/ICDT/ICPGD_13") (pintype "bidirectional"))
    )
    (net (code "69") (name "unconnected-(IC1-NC{slash}ICPORTS-Pad34)") (class "Default")
      (node (ref "IC1") (pin "34") (pinfunction "NC/ICPORTS_34") (pintype "input"))
    )
    (net (code "70") (name "unconnected-(IC1-NC{slash}~{ICRST}{slash}IVVPP-Pad33)") (class "Default")
      (node (ref "IC1") (pin "33") (pinfunction "NC/~{ICRST}/IVVPP_33") (pintype "input"))
    )
    (net (code "71") (name "unconnected-(IC2-CLKOUT-Pad26)") (class "Default")
      (node (ref "IC2") (pin "26") (pinfunction "CLKOUT_26") (pintype "bidirectional"))
    )
    (net (code "72") (name "unconnected-(IC2-GPIO0-Pad7)") (class "Default")
      (node (ref "IC2") (pin "7") (pinfunction "GPIO0_7") (pintype "bidirectional"))
    )
    (net (code "73") (name "unconnected-(IC2-GPIO1-Pad8)") (class "Default")
      (node (ref "IC2") (pin "8") (pinfunction "GPIO1_8") (pintype "bidirectional"))
    )
    (net (code "74") (name "unconnected-(IC2-GPIO2-Pad11)") (class "Default")
      (node (ref "IC2") (pin "11") (pinfunction "GPIO2_11") (pintype "bidirectional"))
    )
    (net (code "75") (name "unconnected-(IC2-GPIO3-Pad12)") (class "Default")
      (node (ref "IC2") (pin "12") (pinfunction "GPIO3_12") (pintype "bidirectional"))
    )
    (net (code "76") (name "unconnected-(IC2-GPIO4-Pad10)") (class "Default")
      (node (ref "IC2") (pin "10") (pinfunction "GPIO4_10") (pintype "bidirectional"))
    )
    (net (code "77") (name "unconnected-(IC2-GPIO5-Pad9)") (class "Default")
      (node (ref "IC2") (pin "9") (pinfunction "GPIO5_9") (pintype "bidirectional"))
    )
    (net (code "78") (name "unconnected-(IC2-LPOSC1-Pad28)") (class "Default")
      (node (ref "IC2") (pin "28") (pinfunction "LPOSC1_28") (pintype "open_collector"))
    )
    (net (code "79") (name "unconnected-(IC2-LPOSC2-Pad27)") (class "Default")
      (node (ref "IC2") (pin "27") (pinfunction "LPOSC2_27") (pintype "open_collector"))
    )
    (net (code "80") (name "unconnected-(IC2-N{slash}C-Pad23)") (class "Default")
      (node (ref "IC2") (pin "23") (pinfunction "N/C_23") (pintype "no_connect"))
    )
    (net (code "81") (name "unconnected-(IC2-N{slash}C-Pad38)") (class "Default")
      (node (ref "IC2") (pin "38") (pinfunction "N/C_38") (pintype "no_connect"))
    )
    (net (code "82") (name "unconnected-(IC2-RXIP-Pad29)") (class "Default")
      (node (ref "IC2") (pin "29") (pinfunction "RXIP_29") (pintype "bidirectional"))
    )
    (net (code "83") (name "unconnected-(IC2-RXQP-Pad30)") (class "Default")
      (node (ref "IC2") (pin "30") (pinfunction "RXQP_30") (pintype "bidirectional"))
    )
    (net (code "84") (name "unconnected-(ICSP-RJ11-Pad6)") (class "Default")
      (node (ref "ICSP-RJ11") (pin "6") (pinfunction "6_6") (pintype "passive"))
    )
    (net (code "85") (name "unconnected-(ISCPF-1-Pad6)") (class "Default")
      (node (ref "ISCP") (pin "6") (pinfunction "1_6") (pintype "passive"))
    )
    (net (code "86") (name "unconnected-(PB1-Pad1)") (class "Default")
      (node (ref "PB1") (pin "1") (pinfunction "1_1") (pintype "passive"))
    )
    (net (code "87") (name "unconnected-(PB1-Pad2)") (class "Default")
      (node (ref "PB1") (pin "2") (pinfunction "2_2") (pintype "passive"))
    )
    (net (code "88") (name "unconnected-(PB1-Pad3)") (class "Default")
      (node (ref "PB1") (pin "3") (pinfunction "3_3") (pintype "passive"))
    )
    (net (code "89") (name "unconnected-(PB1-Pad4)") (class "Default")
      (node (ref "PB1") (pin "4") (pinfunction "4_4") (pintype "passive"))
    )
    (net (code "90") (name "unconnected-(PB1-Pad5)") (class "Default")
      (node (ref "PB1") (pin "5") (pinfunction "5_5") (pintype "passive"))
    )
    (net (code "91") (name "unconnected-(PB1-Pad6)") (class "Default")
      (node (ref "PB1") (pin "6") (pinfunction "6_6") (pintype "passive"))
    )
    (net (code "92") (name "unconnected-(PB1-Pad7)") (class "Default")
      (node (ref "PB1") (pin "7") (pinfunction "7_7") (pintype "passive"))
    )
    (net (code "93") (name "unconnected-(PB1-Pad8)") (class "Default")
      (node (ref "PB1") (pin "8") (pinfunction "8_8") (pintype "passive"))
    )
    (net (code "94") (name "unconnected-(PB1-Pad9)") (class "Default")
      (node (ref "PB1") (pin "9") (pinfunction "9_9") (pintype "passive"))
    )
    (net (code "95") (name "unconnected-(PB1-Pad10)") (class "Default")
      (node (ref "PB1") (pin "10") (pinfunction "10_10") (pintype "passive"))
    )
    (net (code "96") (name "unconnected-(PB1-Pad11)") (class "Default")
      (node (ref "PB1") (pin "11") (pinfunction "11_11") (pintype "passive"))
    )
    (net (code "97") (name "unconnected-(PB1-Pad12)") (class "Default")
      (node (ref "PB1") (pin "12") (pinfunction "12_12") (pintype "passive"))
    )
    (net (code "98") (name "unconnected-(PB1-Pad13)") (class "Default")
      (node (ref "PB1") (pin "13") (pinfunction "13_13") (pintype "passive"))
    )
    (net (code "99") (name "unconnected-(PB1-Pad14)") (class "Default")
      (node (ref "PB1") (pin "14") (pinfunction "14_14") (pintype "passive"))
    )
    (net (code "100") (name "unconnected-(PB1-Pad15)") (class "Default")
      (node (ref "PB1") (pin "15") (pinfunction "15_15") (pintype "passive"))
    )
    (net (code "101") (name "unconnected-(PB1-Pad16)") (class "Default")
      (node (ref "PB1") (pin "16") (pinfunction "16_16") (pintype "passive"))
    )
    (net (code "102") (name "unconnected-(PB1-Pad17)") (class "Default")
      (node (ref "PB1") (pin "17") (pinfunction "17_17") (pintype "passive"))
    )
    (net (code "103") (name "unconnected-(PB1-Pad18)") (class "Default")
      (node (ref "PB1") (pin "18") (pinfunction "18_18") (pintype "passive"))
    )
    (net (code "104") (name "unconnected-(PB1-Pad19)") (class "Default")
      (node (ref "PB1") (pin "19") (pinfunction "19_19") (pintype "passive"))
    )
    (net (code "105") (name "unconnected-(PB1-Pad20)") (class "Default")
      (node (ref "PB1") (pin "20") (pinfunction "20_20") (pintype "passive"))
    )
    (net (code "106") (name "unconnected-(PB1-Pad21)") (class "Default")
      (node (ref "PB1") (pin "21") (pinfunction "21_21") (pintype "passive"))
    )
    (net (code "107") (name "unconnected-(PB1-Pad22)") (class "Default")
      (node (ref "PB1") (pin "22") (pinfunction "22_22") (pintype "passive"))
    )
    (net (code "108") (name "unconnected-(PB1-Pad23)") (class "Default")
      (node (ref "PB1") (pin "23") (pinfunction "23_23") (pintype "passive"))
    )
    (net (code "109") (name "unconnected-(PB1-Pad24)") (class "Default")
      (node (ref "PB1") (pin "24") (pinfunction "24_24") (pintype "passive"))
    )
    (net (code "110") (name "unconnected-(PB1-Pad25)") (class "Default")
      (node (ref "PB1") (pin "25") (pinfunction "25_25") (pintype "passive"))
    )
    (net (code "111") (name "unconnected-(PB1-Pad26)") (class "Default")
      (node (ref "PB1") (pin "26") (pinfunction "26_26") (pintype "passive"))
    )
    (net (code "112") (name "unconnected-(PB1-Pad27)") (class "Default")
      (node (ref "PB1") (pin "27") (pinfunction "27_27") (pintype "passive"))
    )
    (net (code "113") (name "unconnected-(PB1-Pad28)") (class "Default")
      (node (ref "PB1") (pin "28") (pinfunction "28_28") (pintype "passive"))
    )
    (net (code "114") (name "unconnected-(PB1-Pad29)") (class "Default")
      (node (ref "PB1") (pin "29") (pinfunction "29_29") (pintype "passive"))
    )
    (net (code "115") (name "unconnected-(PB1-Pad30)") (class "Default")
      (node (ref "PB1") (pin "30") (pinfunction "30_30") (pintype "passive"))
    )
    (net (code "116") (name "unconnected-(PB1-Pad31)") (class "Default")
      (node (ref "PB1") (pin "31") (pinfunction "31_31") (pintype "passive"))
    )
    (net (code "117") (name "unconnected-(PB1-Pad32)") (class "Default")
      (node (ref "PB1") (pin "32") (pinfunction "32_32") (pintype "passive"))
    )
    (net (code "118") (name "unconnected-(PB1-Pad33)") (class "Default")
      (node (ref "PB1") (pin "33") (pinfunction "33_33") (pintype "passive"))
    )
    (net (code "119") (name "unconnected-(PB1-Pad34)") (class "Default")
      (node (ref "PB1") (pin "34") (pinfunction "34_34") (pintype "passive"))
    )
    (net (code "120") (name "unconnected-(PB2-Pad1)") (class "Default")
      (node (ref "PB2") (pin "1") (pinfunction "1_1") (pintype "passive"))
    )
    (net (code "121") (name "unconnected-(PB2-Pad2)") (class "Default")
      (node (ref "PB2") (pin "2") (pinfunction "2_2") (pintype "passive"))
    )
    (net (code "122") (name "unconnected-(PB2-Pad3)") (class "Default")
      (node (ref "PB2") (pin "3") (pinfunction "3_3") (pintype "passive"))
    )
    (net (code "123") (name "unconnected-(PB2-Pad4)") (class "Default")
      (node (ref "PB2") (pin "4") (pinfunction "4_4") (pintype "passive"))
    )
    (net (code "124") (name "unconnected-(PB2-Pad5)") (class "Default")
      (node (ref "PB2") (pin "5") (pinfunction "5_5") (pintype "passive"))
    )
    (net (code "125") (name "unconnected-(PB2-Pad6)") (class "Default")
      (node (ref "PB2") (pin "6") (pinfunction "6_6") (pintype "passive"))
    )
    (net (code "126") (name "unconnected-(PB2-Pad7)") (class "Default")
      (node (ref "PB2") (pin "7") (pinfunction "7_7") (pintype "passive"))
    )
    (net (code "127") (name "unconnected-(PB2-Pad8)") (class "Default")
      (node (ref "PB2") (pin "8") (pinfunction "8_8") (pintype "passive"))
    )
    (net (code "128") (name "unconnected-(PB2-Pad9)") (class "Default")
      (node (ref "PB2") (pin "9") (pinfunction "9_9") (pintype "passive"))
    )
    (net (code "129") (name "unconnected-(PB2-Pad10)") (class "Default")
      (node (ref "PB2") (pin "10") (pinfunction "10_10") (pintype "passive"))
    )
    (net (code "130") (name "unconnected-(PB2-Pad11)") (class "Default")
      (node (ref "PB2") (pin "11") (pinfunction "11_11") (pintype "passive"))
    )
    (net (code "131") (name "unconnected-(PB2-Pad12)") (class "Default")
      (node (ref "PB2") (pin "12") (pinfunction "12_12") (pintype "passive"))
    )
    (net (code "132") (name "unconnected-(PB2-Pad13)") (class "Default")
      (node (ref "PB2") (pin "13") (pinfunction "13_13") (pintype "passive"))
    )
    (net (code "133") (name "unconnected-(PB2-Pad14)") (class "Default")
      (node (ref "PB2") (pin "14") (pinfunction "14_14") (pintype "passive"))
    )
    (net (code "134") (name "unconnected-(PB2-Pad15)") (class "Default")
      (node (ref "PB2") (pin "15") (pinfunction "15_15") (pintype "passive"))
    )
    (net (code "135") (name "unconnected-(PB2-Pad16)") (class "Default")
      (node (ref "PB2") (pin "16") (pinfunction "16_16") (pintype "passive"))
    )
    (net (code "136") (name "unconnected-(PB2-Pad17)") (class "Default")
      (node (ref "PB2") (pin "17") (pinfunction "17_17") (pintype "passive"))
    )
    (net (code "137") (name "unconnected-(PB2-Pad18)") (class "Default")
      (node (ref "PB2") (pin "18") (pinfunction "18_18") (pintype "passive"))
    )
    (net (code "138") (name "unconnected-(PB2-Pad19)") (class "Default")
      (node (ref "PB2") (pin "19") (pinfunction "19_19") (pintype "passive"))
    )
    (net (code "139") (name "unconnected-(PB2-Pad20)") (class "Default")
      (node (ref "PB2") (pin "20") (pinfunction "20_20") (pintype "passive"))
    )
    (net (code "140") (name "unconnected-(PB2-Pad21)") (class "Default")
      (node (ref "PB2") (pin "21") (pinfunction "21_21") (pintype "passive"))
    )
    (net (code "141") (name "unconnected-(PB2-Pad22)") (class "Default")
      (node (ref "PB2") (pin "22") (pinfunction "22_22") (pintype "passive"))
    )
    (net (code "142") (name "unconnected-(PB2-Pad23)") (class "Default")
      (node (ref "PB2") (pin "23") (pinfunction "23_23") (pintype "passive"))
    )
    (net (code "143") (name "unconnected-(PB2-Pad24)") (class "Default")
      (node (ref "PB2") (pin "24") (pinfunction "24_24") (pintype "passive"))
    )
    (net (code "144") (name "unconnected-(PB2-Pad25)") (class "Default")
      (node (ref "PB2") (pin "25") (pinfunction "25_25") (pintype "passive"))
    )
    (net (code "145") (name "unconnected-(PB2-Pad26)") (class "Default")
      (node (ref "PB2") (pin "26") (pinfunction "26_26") (pintype "passive"))
    )
    (net (code "146") (name "unconnected-(PB2-Pad27)") (class "Default")
      (node (ref "PB2") (pin "27") (pinfunction "27_27") (pintype "passive"))
    )
    (net (code "147") (name "unconnected-(PB2-Pad28)") (class "Default")
      (node (ref "PB2") (pin "28") (pinfunction "28_28") (pintype "passive"))
    )
    (net (code "148") (name "unconnected-(PB2-Pad29)") (class "Default")
      (node (ref "PB2") (pin "29") (pinfunction "29_29") (pintype "passive"))
    )
    (net (code "149") (name "unconnected-(PB2-Pad30)") (class "Default")
      (node (ref "PB2") (pin "30") (pinfunction "30_30") (pintype "passive"))
    )
    (net (code "150") (name "unconnected-(PB2-Pad31)") (class "Default")
      (node (ref "PB2") (pin "31") (pinfunction "31_31") (pintype "passive"))
    )
    (net (code "151") (name "unconnected-(PB2-Pad32)") (class "Default")
      (node (ref "PB2") (pin "32") (pinfunction "32_32") (pintype "passive"))
    )
    (net (code "152") (name "unconnected-(PB2-Pad33)") (class "Default")
      (node (ref "PB2") (pin "33") (pinfunction "33_33") (pintype "passive"))
    )
    (net (code "153") (name "unconnected-(PB2-Pad34)") (class "Default")
      (node (ref "PB2") (pin "34") (pinfunction "34_34") (pintype "passive"))
    )
    (net (code "154") (name "unconnected-(PB3-Pad1)") (class "Default")
      (node (ref "PB3") (pin "1") (pinfunction "1_1") (pintype "passive"))
    )
    (net (code "155") (name "unconnected-(PB3-Pad2)") (class "Default")
      (node (ref "PB3") (pin "2") (pinfunction "2_2") (pintype "passive"))
    )
    (net (code "156") (name "unconnected-(PB3-Pad3)") (class "Default")
      (node (ref "PB3") (pin "3") (pinfunction "3_3") (pintype "passive"))
    )
    (net (code "157") (name "unconnected-(PB3-Pad4)") (class "Default")
      (node (ref "PB3") (pin "4") (pinfunction "4_4") (pintype "passive"))
    )
    (net (code "158") (name "unconnected-(PB3-Pad5)") (class "Default")
      (node (ref "PB3") (pin "5") (pinfunction "5_5") (pintype "passive"))
    )
    (net (code "159") (name "unconnected-(PB3-Pad6)") (class "Default")
      (node (ref "PB3") (pin "6") (pinfunction "6_6") (pintype "passive"))
    )
    (net (code "160") (name "unconnected-(PB3-Pad7)") (class "Default")
      (node (ref "PB3") (pin "7") (pinfunction "7_7") (pintype "passive"))
    )
    (net (code "161") (name "unconnected-(PB3-Pad8)") (class "Default")
      (node (ref "PB3") (pin "8") (pinfunction "8_8") (pintype "passive"))
    )
    (net (code "162") (name "unconnected-(PB3-Pad9)") (class "Default")
      (node (ref "PB3") (pin "9") (pinfunction "9_9") (pintype "passive"))
    )
    (net (code "163") (name "unconnected-(PB3-Pad10)") (class "Default")
      (node (ref "PB3") (pin "10") (pinfunction "10_10") (pintype "passive"))
    )
    (net (code "164") (name "unconnected-(PB3-Pad11)") (class "Default")
      (node (ref "PB3") (pin "11") (pinfunction "11_11") (pintype "passive"))
    )
    (net (code "165") (name "unconnected-(PB3-Pad12)") (class "Default")
      (node (ref "PB3") (pin "12") (pinfunction "12_12") (pintype "passive"))
    )
    (net (code "166") (name "unconnected-(PB3-Pad13)") (class "Default")
      (node (ref "PB3") (pin "13") (pinfunction "13_13") (pintype "passive"))
    )
    (net (code "167") (name "unconnected-(PB3-Pad14)") (class "Default")
      (node (ref "PB3") (pin "14") (pinfunction "14_14") (pintype "passive"))
    )
    (net (code "168") (name "unconnected-(PB3-Pad15)") (class "Default")
      (node (ref "PB3") (pin "15") (pinfunction "15_15") (pintype "passive"))
    )
    (net (code "169") (name "unconnected-(PB3-Pad16)") (class "Default")
      (node (ref "PB3") (pin "16") (pinfunction "16_16") (pintype "passive"))
    )
    (net (code "170") (name "unconnected-(PB3-Pad17)") (class "Default")
      (node (ref "PB3") (pin "17") (pinfunction "17_17") (pintype "passive"))
    )
    (net (code "171") (name "unconnected-(PB3-Pad18)") (class "Default")
      (node (ref "PB3") (pin "18") (pinfunction "18_18") (pintype "passive"))
    )
    (net (code "172") (name "unconnected-(PB3-Pad19)") (class "Default")
      (node (ref "PB3") (pin "19") (pinfunction "19_19") (pintype "passive"))
    )
    (net (code "173") (name "unconnected-(PB3-Pad20)") (class "Default")
      (node (ref "PB3") (pin "20") (pinfunction "20_20") (pintype "passive"))
    )
    (net (code "174") (name "unconnected-(PB3-Pad21)") (class "Default")
      (node (ref "PB3") (pin "21") (pinfunction "21_21") (pintype "passive"))
    )
    (net (code "175") (name "unconnected-(PB3-Pad22)") (class "Default")
      (node (ref "PB3") (pin "22") (pinfunction "22_22") (pintype "passive"))
    )
    (net (code "176") (name "unconnected-(PB3-Pad23)") (class "Default")
      (node (ref "PB3") (pin "23") (pinfunction "23_23") (pintype "passive"))
    )
    (net (code "177") (name "unconnected-(PB3-Pad24)") (class "Default")
      (node (ref "PB3") (pin "24") (pinfunction "24_24") (pintype "passive"))
    )
    (net (code "178") (name "unconnected-(PB3-Pad25)") (class "Default")
      (node (ref "PB3") (pin "25") (pinfunction "25_25") (pintype "passive"))
    )
    (net (code "179") (name "unconnected-(PB3-Pad26)") (class "Default")
      (node (ref "PB3") (pin "26") (pinfunction "26_26") (pintype "passive"))
    )
    (net (code "180") (name "unconnected-(PB3-Pad27)") (class "Default")
      (node (ref "PB3") (pin "27") (pinfunction "27_27") (pintype "passive"))
    )
    (net (code "181") (name "unconnected-(PB3-Pad28)") (class "Default")
      (node (ref "PB3") (pin "28") (pinfunction "28_28") (pintype "passive"))
    )
    (net (code "182") (name "unconnected-(PB3-Pad29)") (class "Default")
      (node (ref "PB3") (pin "29") (pinfunction "29_29") (pintype "passive"))
    )
    (net (code "183") (name "unconnected-(PB3-Pad30)") (class "Default")
      (node (ref "PB3") (pin "30") (pinfunction "30_30") (pintype "passive"))
    )
    (net (code "184") (name "unconnected-(PB3-Pad31)") (class "Default")
      (node (ref "PB3") (pin "31") (pinfunction "31_31") (pintype "passive"))
    )
    (net (code "185") (name "unconnected-(PB3-Pad32)") (class "Default")
      (node (ref "PB3") (pin "32") (pinfunction "32_32") (pintype "passive"))
    )
    (net (code "186") (name "unconnected-(PB3-Pad33)") (class "Default")
      (node (ref "PB3") (pin "33") (pinfunction "33_33") (pintype "passive"))
    )
    (net (code "187") (name "unconnected-(PB3-Pad34)") (class "Default")
      (node (ref "PB3") (pin "34") (pinfunction "34_34") (pintype "passive"))
    )
    (net (code "188") (name "unconnected-(PB4-Pad1)") (class "Default")
      (node (ref "PB4") (pin "1") (pinfunction "1_1") (pintype "passive"))
    )
    (net (code "189") (name "unconnected-(PB4-Pad2)") (class "Default")
      (node (ref "PB4") (pin "2") (pinfunction "2_2") (pintype "passive"))
    )
    (net (code "190") (name "unconnected-(PB4-Pad3)") (class "Default")
      (node (ref "PB4") (pin "3") (pinfunction "3_3") (pintype "passive"))
    )
    (net (code "191") (name "unconnected-(PB4-Pad4)") (class "Default")
      (node (ref "PB4") (pin "4") (pinfunction "4_4") (pintype "passive"))
    )
    (net (code "192") (name "unconnected-(PB4-Pad5)") (class "Default")
      (node (ref "PB4") (pin "5") (pinfunction "5_5") (pintype "passive"))
    )
    (net (code "193") (name "unconnected-(PB4-Pad6)") (class "Default")
      (node (ref "PB4") (pin "6") (pinfunction "6_6") (pintype "passive"))
    )
    (net (code "194") (name "unconnected-(PB4-Pad7)") (class "Default")
      (node (ref "PB4") (pin "7") (pinfunction "7_7") (pintype "passive"))
    )
    (net (code "195") (name "unconnected-(PB4-Pad8)") (class "Default")
      (node (ref "PB4") (pin "8") (pinfunction "8_8") (pintype "passive"))
    )
    (net (code "196") (name "unconnected-(PB4-Pad9)") (class "Default")
      (node (ref "PB4") (pin "9") (pinfunction "9_9") (pintype "passive"))
    )
    (net (code "197") (name "unconnected-(PB4-Pad10)") (class "Default")
      (node (ref "PB4") (pin "10") (pinfunction "10_10") (pintype "passive"))
    )
    (net (code "198") (name "unconnected-(PB4-Pad11)") (class "Default")
      (node (ref "PB4") (pin "11") (pinfunction "11_11") (pintype "passive"))
    )
    (net (code "199") (name "unconnected-(PB4-Pad12)") (class "Default")
      (node (ref "PB4") (pin "12") (pinfunction "12_12") (pintype "passive"))
    )
    (net (code "200") (name "unconnected-(PB4-Pad13)") (class "Default")
      (node (ref "PB4") (pin "13") (pinfunction "13_13") (pintype "passive"))
    )
    (net (code "201") (name "unconnected-(PB4-Pad14)") (class "Default")
      (node (ref "PB4") (pin "14") (pinfunction "14_14") (pintype "passive"))
    )
    (net (code "202") (name "unconnected-(PB4-Pad15)") (class "Default")
      (node (ref "PB4") (pin "15") (pinfunction "15_15") (pintype "passive"))
    )
    (net (code "203") (name "unconnected-(PB4-Pad16)") (class "Default")
      (node (ref "PB4") (pin "16") (pinfunction "16_16") (pintype "passive"))
    )
    (net (code "204") (name "unconnected-(PB4-Pad17)") (class "Default")
      (node (ref "PB4") (pin "17") (pinfunction "17_17") (pintype "passive"))
    )
    (net (code "205") (name "unconnected-(PB4-Pad18)") (class "Default")
      (node (ref "PB4") (pin "18") (pinfunction "18_18") (pintype "passive"))
    )
    (net (code "206") (name "unconnected-(PB4-Pad19)") (class "Default")
      (node (ref "PB4") (pin "19") (pinfunction "19_19") (pintype "passive"))
    )
    (net (code "207") (name "unconnected-(PB4-Pad20)") (class "Default")
      (node (ref "PB4") (pin "20") (pinfunction "20_20") (pintype "passive"))
    )
    (net (code "208") (name "unconnected-(PB4-Pad21)") (class "Default")
      (node (ref "PB4") (pin "21") (pinfunction "21_21") (pintype "passive"))
    )
    (net (code "209") (name "unconnected-(PB4-Pad22)") (class "Default")
      (node (ref "PB4") (pin "22") (pinfunction "22_22") (pintype "passive"))
    )
    (net (code "210") (name "unconnected-(PB4-Pad23)") (class "Default")
      (node (ref "PB4") (pin "23") (pinfunction "23_23") (pintype "passive"))
    )
    (net (code "211") (name "unconnected-(PB4-Pad24)") (class "Default")
      (node (ref "PB4") (pin "24") (pinfunction "24_24") (pintype "passive"))
    )
    (net (code "212") (name "unconnected-(PB4-Pad25)") (class "Default")
      (node (ref "PB4") (pin "25") (pinfunction "25_25") (pintype "passive"))
    )
    (net (code "213") (name "unconnected-(PB4-Pad26)") (class "Default")
      (node (ref "PB4") (pin "26") (pinfunction "26_26") (pintype "passive"))
    )
    (net (code "214") (name "unconnected-(PB4-Pad27)") (class "Default")
      (node (ref "PB4") (pin "27") (pinfunction "27_27") (pintype "passive"))
    )
    (net (code "215") (name "unconnected-(PB4-Pad28)") (class "Default")
      (node (ref "PB4") (pin "28") (pinfunction "28_28") (pintype "passive"))
    )
    (net (code "216") (name "unconnected-(PB4-Pad29)") (class "Default")
      (node (ref "PB4") (pin "29") (pinfunction "29_29") (pintype "passive"))
    )
    (net (code "217") (name "unconnected-(PB4-Pad30)") (class "Default")
      (node (ref "PB4") (pin "30") (pinfunction "30_30") (pintype "passive"))
    )
    (net (code "218") (name "unconnected-(PB4-Pad31)") (class "Default")
      (node (ref "PB4") (pin "31") (pinfunction "31_31") (pintype "passive"))
    )
    (net (code "219") (name "unconnected-(PB4-Pad32)") (class "Default")
      (node (ref "PB4") (pin "32") (pinfunction "32_32") (pintype "passive"))
    )
    (net (code "220") (name "unconnected-(PB4-Pad33)") (class "Default")
      (node (ref "PB4") (pin "33") (pinfunction "33_33") (pintype "passive"))
    )
    (net (code "221") (name "unconnected-(PB4-Pad34)") (class "Default")
      (node (ref "PB4") (pin "34") (pinfunction "34_34") (pintype "passive"))
    )
    (net (code "222") (name "unconnected-(U$2-MTN1-PadMTN3)") (class "Default")
      (node (ref "U$2") (pin "MTN3") (pinfunction "MTN1_MTN3") (pintype "bidirectional"))
    )
    (net (code "223") (name "unconnected-(U$2-MTN2-PadMTN1)") (class "Default")
      (node (ref "U$2") (pin "MTN1") (pinfunction "MTN2_MTN1") (pintype "bidirectional"))
    )
    (net (code "224") (name "unconnected-(U$2-MTN3-PadMTN2)") (class "Default")
      (node (ref "U$2") (pin "MTN2") (pinfunction "MTN3_MTN2") (pintype "bidirectional"))
    )
    (net (code "225") (name "unconnected-(U$2-PadD+)") (class "Default")
      (node (ref "U$2") (pin "D+") (pinfunction "D+_D+") (pintype "bidirectional"))
    )
    (net (code "226") (name "unconnected-(U$2-PadD-)") (class "Default")
      (node (ref "U$2") (pin "D-") (pinfunction "D-_D-") (pintype "bidirectional"))
    )
    (net (code "227") (name "unconnected-(U$2-PadID)") (class "Default")
      (node (ref "U$2") (pin "ID") (pinfunction "ID_ID") (pintype "bidirectional"))
    )
    (net (code "228") (name "unconnected-(U$2-PadMTN4)") (class "Default")
      (node (ref "U$2") (pin "MTN4") (pinfunction "MTN4_MTN4") (pintype "bidirectional"))
    )
  )
)
